# Group_9_Bastiaens_Castiaux_Danthine_Peti.net
KiCad netlist of a schematic drawn in EAGLE
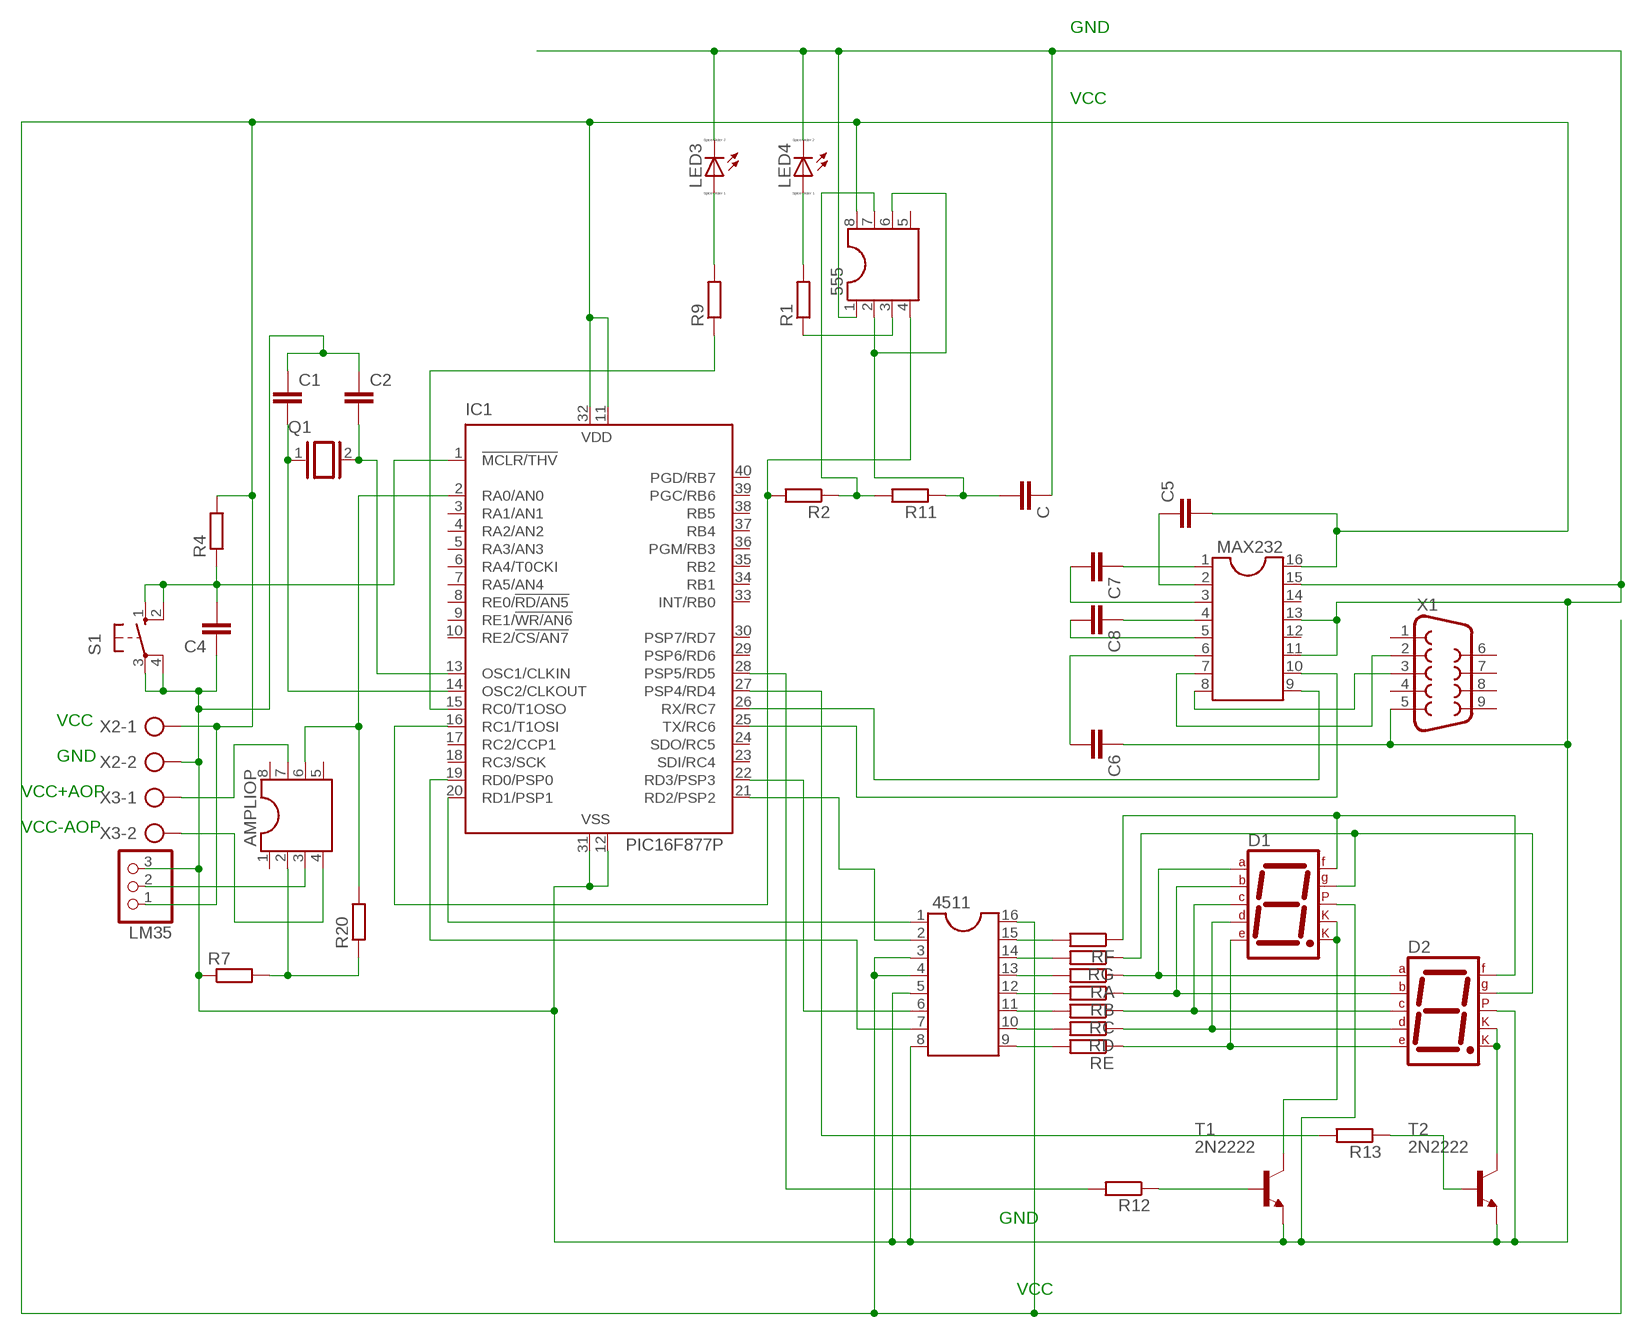
[diagram p0: schematic, sheet 1]

(export (version "E")
  (design (tool "Eeschema 10.0.6"))
  (components
    (comp (ref "555")
      (value "DIL8")
      (footprint "eagle-import:DIL08")
      (libsource (lib "eagle-import") (part "DIL8"))
    )
    (comp (ref "4511")
      (value "DIL16")
      (footprint "eagle-import:DIL16")
      (libsource (lib "eagle-import") (part "DIL16"))
    )
    (comp (ref "AMPLIOP")
      (value "DIL8")
      (footprint "eagle-import:DIL08")
      (libsource (lib "eagle-import") (part "DIL8"))
    )
    (comp (ref "C")
      (value "C-EU025-050X050")
      (footprint "eagle-import:C025-050X050")
      (libsource (lib "eagle-import") (part "C-EU025-050X050"))
    )
    (comp (ref "C1")
      (value "C-EU025-050X050")
      (footprint "eagle-import:C025-050X050")
      (libsource (lib "eagle-import") (part "C-EU025-050X050"))
    )
    (comp (ref "C2")
      (value "C-EU025-050X050")
      (footprint "eagle-import:C025-050X050")
      (libsource (lib "eagle-import") (part "C-EU025-050X050"))
    )
    (comp (ref "C4")
      (value "C-EU025-050X050")
      (footprint "eagle-import:C025-050X050")
      (libsource (lib "eagle-import") (part "C-EU025-050X050"))
    )
    (comp (ref "C5")
      (value "C-EU025-050X050")
      (footprint "eagle-import:C025-050X050")
      (libsource (lib "eagle-import") (part "C-EU025-050X050"))
    )
    (comp (ref "C6")
      (value "C-EU025-050X050")
      (footprint "eagle-import:C025-050X050")
      (libsource (lib "eagle-import") (part "C-EU025-050X050"))
    )
    (comp (ref "C7")
      (value "C-EU025-050X050")
      (footprint "eagle-import:C025-050X050")
      (libsource (lib "eagle-import") (part "C-EU025-050X050"))
    )
    (comp (ref "C8")
      (value "C-EU025-050X050")
      (footprint "eagle-import:C025-050X050")
      (libsource (lib "eagle-import") (part "C-EU025-050X050"))
    )
    (comp (ref "D1")
      (value "7SEG-CK")
      (footprint "eagle-import:7SEG-13")
      (libsource (lib "eagle-import") (part "7SEG-CK"))
    )
    (comp (ref "D2")
      (value "7SEG-CK")
      (footprint "eagle-import:7SEG-13")
      (libsource (lib "eagle-import") (part "7SEG-CK"))
    )
    (comp (ref "IC1")
      (value "PIC16F877P")
      (footprint "eagle-import:DIL40")
      (fields (field (name "MF") "MICROCHIP") (field (name "MPN") "PIC16F877-04/P"))
      (libsource (lib "eagle-import") (part "PIC16F87P7"))
    )
    (comp (ref "LED3")
      (value "LED_ELD260")
      (footprint "eagle-import:LED_LD260")
      (libsource (lib "eagle-import") (part "LED_ELD260"))
    )
    (comp (ref "LED4")
      (value "LED_ELD260")
      (footprint "eagle-import:LED_LD260")
      (libsource (lib "eagle-import") (part "LED_ELD260"))
    )
    (comp (ref "LM35")
      (value "PINHD-1X3")
      (footprint "eagle-import:1X03")
      (libsource (lib "eagle-import") (part "PINHD-1X3"))
    )
    (comp (ref "MAX232")
      (value "DIL16")
      (footprint "eagle-import:DIL16")
      (libsource (lib "eagle-import") (part "DIL16"))
    )
    (comp (ref "Q1")
      (value "XTAL/S")
      (footprint "eagle-import:QS")
      (libsource (lib "eagle-import") (part "XTAL/S"))
    )
    (comp (ref "R1")
      (value "R-EU_0204/7")
      (footprint "eagle-import:0204_7")
      (libsource (lib "eagle-import") (part "R-EU_0204/7"))
    )
    (comp (ref "R2")
      (value "R-EU_0204/7")
      (footprint "eagle-import:0204_7")
      (libsource (lib "eagle-import") (part "R-EU_0204/7"))
    )
    (comp (ref "R4")
      (value "R-EU_0204/7")
      (footprint "eagle-import:0204_7")
      (libsource (lib "eagle-import") (part "R-EU_0204/7"))
    )
    (comp (ref "R7")
      (value "R-EU_0204/7")
      (footprint "eagle-import:0204_7")
      (libsource (lib "eagle-import") (part "R-EU_0204/7"))
    )
    (comp (ref "R9")
      (value "R-EU_0204/7")
      (footprint "eagle-import:0204_7")
      (libsource (lib "eagle-import") (part "R-EU_0204/7"))
    )
    (comp (ref "R11")
      (value "R-EU_0204/7")
      (footprint "eagle-import:0204_7")
      (libsource (lib "eagle-import") (part "R-EU_0204/7"))
    )
    (comp (ref "R12")
      (value "R-EU_0204/7")
      (footprint "eagle-import:0204_7")
      (libsource (lib "eagle-import") (part "R-EU_0204/7"))
    )
    (comp (ref "R13")
      (value "R-EU_0204/7")
      (footprint "eagle-import:0204_7")
      (libsource (lib "eagle-import") (part "R-EU_0204/7"))
    )
    (comp (ref "R20")
      (value "R-EU_0204/7")
      (footprint "eagle-import:0204_7")
      (libsource (lib "eagle-import") (part "R-EU_0204/7"))
    )
    (comp (ref "RA")
      (value "R-EU_0204/7")
      (footprint "eagle-import:0204_7")
      (libsource (lib "eagle-import") (part "R-EU_0204/7"))
    )
    (comp (ref "RB")
      (value "R-EU_0204/7")
      (footprint "eagle-import:0204_7")
      (libsource (lib "eagle-import") (part "R-EU_0204/7"))
    )
    (comp (ref "RC")
      (value "R-EU_0204/7")
      (footprint "eagle-import:0204_7")
      (libsource (lib "eagle-import") (part "R-EU_0204/7"))
    )
    (comp (ref "RD")
      (value "R-EU_0204/7")
      (footprint "eagle-import:0204_7")
      (libsource (lib "eagle-import") (part "R-EU_0204/7"))
    )
    (comp (ref "RE")
      (value "R-EU_0204/7")
      (footprint "eagle-import:0204_7")
      (libsource (lib "eagle-import") (part "R-EU_0204/7"))
    )
    (comp (ref "RF")
      (value "R-EU_0204/7")
      (footprint "eagle-import:0204_7")
      (libsource (lib "eagle-import") (part "R-EU_0204/7"))
    )
    (comp (ref "RG")
      (value "R-EU_0204/7")
      (footprint "eagle-import:0204_7")
      (libsource (lib "eagle-import") (part "R-EU_0204/7"))
    )
    (comp (ref "S1")
      (value "10-XX")
      (footprint "eagle-import:B3F-10XX")
      (fields (field (name "MPN") "B3F-1000"))
      (libsource (lib "eagle-import") (part "10-XX"))
    )
    (comp (ref "T1")
      (value "2N2222")
      (footprint "eagle-import:TO18")
      (libsource (lib "eagle-import") (part "2N2222"))
    )
    (comp (ref "T2")
      (value "2N2222")
      (footprint "eagle-import:TO18")
      (libsource (lib "eagle-import") (part "2N2222"))
    )
    (comp (ref "X1")
      (value "F09V")
      (footprint "eagle-import:F09V")
      (libsource (lib "eagle-import") (part "F09V"))
    )
    (comp (ref "X2")
      (value "AK300/2")
      (footprint "eagle-import:AK300_2")
      (libsource (lib "eagle-import") (part "AK300/2"))
    )
    (comp (ref "X3")
      (value "AK300/2")
      (footprint "eagle-import:AK300_2")
      (libsource (lib "eagle-import") (part "AK300/2"))
    )
  )
  (nets
    (net (code "1") (name "Net-(555-Pad2)") (class "Default")
      (node (ref "555") (pin "2") (pinfunction "2_2") (pintype "passive"))
      (node (ref "555") (pin "6") (pinfunction "6_6") (pintype "passive"))
      (node (ref "C") (pin "2") (pinfunction "2_2") (pintype "passive"))
      (node (ref "R11") (pin "1") (pinfunction "1_1") (pintype "passive"))
    )
    (net (code "2") (name "Net-(555-Pad3)") (class "Default")
      (node (ref "555") (pin "3") (pinfunction "3_3") (pintype "passive"))
      (node (ref "R1") (pin "1") (pinfunction "1_1") (pintype "passive"))
    )
    (net (code "3") (name "Net-(555-Pad7)") (class "Default")
      (node (ref "555") (pin "7") (pinfunction "7_7") (pintype "passive"))
      (node (ref "R11") (pin "2") (pinfunction "2_2") (pintype "passive"))
      (node (ref "R2") (pin "1") (pinfunction "1_1") (pintype "passive"))
    )
    (net (code "4") (name "Net-(4511-Pad9)") (class "Default")
      (node (ref "4511") (pin "9") (pinfunction "9_9") (pintype "passive"))
      (node (ref "RE") (pin "2") (pinfunction "2_2") (pintype "passive"))
    )
    (net (code "5") (name "Net-(4511-Pad10)") (class "Default")
      (node (ref "4511") (pin "10") (pinfunction "10_10") (pintype "passive"))
      (node (ref "RD") (pin "2") (pinfunction "2_2") (pintype "passive"))
    )
    (net (code "6") (name "Net-(4511-Pad11)") (class "Default")
      (node (ref "4511") (pin "11") (pinfunction "11_11") (pintype "passive"))
      (node (ref "RC") (pin "2") (pinfunction "2_2") (pintype "passive"))
    )
    (net (code "7") (name "Net-(4511-Pad12)") (class "Default")
      (node (ref "4511") (pin "12") (pinfunction "12_12") (pintype "passive"))
      (node (ref "RB") (pin "2") (pinfunction "2_2") (pintype "passive"))
    )
    (net (code "8") (name "Net-(4511-Pad13)") (class "Default")
      (node (ref "4511") (pin "13") (pinfunction "13_13") (pintype "passive"))
      (node (ref "RA") (pin "2") (pinfunction "2_2") (pintype "passive"))
    )
    (net (code "9") (name "Net-(4511-Pad14)") (class "Default")
      (node (ref "4511") (pin "14") (pinfunction "14_14") (pintype "passive"))
      (node (ref "RG") (pin "2") (pinfunction "2_2") (pintype "passive"))
    )
    (net (code "10") (name "Net-(4511-Pad15)") (class "Default")
      (node (ref "4511") (pin "15") (pinfunction "15_15") (pintype "passive"))
      (node (ref "RF") (pin "2") (pinfunction "2_2") (pintype "passive"))
    )
    (net (code "11") (name "Net-(AMPLIOP-Pad2)") (class "Default")
      (node (ref "AMPLIOP") (pin "2") (pinfunction "2_2") (pintype "passive"))
      (node (ref "R20") (pin "1") (pinfunction "1_1") (pintype "passive"))
      (node (ref "R7") (pin "2") (pinfunction "2_2") (pintype "passive"))
    )
    (net (code "12") (name "Net-(AMPLIOP-Pad3)") (class "Default")
      (node (ref "AMPLIOP") (pin "3") (pinfunction "3_3") (pintype "passive"))
      (node (ref "LM35") (pin "2") (pinfunction "2_2") (pintype "passive"))
    )
    (net (code "13") (name "Net-(C5-Pad1)") (class "Default")
      (node (ref "C5") (pin "1") (pinfunction "1_1") (pintype "passive"))
      (node (ref "MAX232") (pin "2") (pinfunction "2_2") (pintype "passive"))
    )
    (net (code "14") (name "Net-(C6-Pad2)") (class "Default")
      (node (ref "C6") (pin "2") (pinfunction "2_2") (pintype "passive"))
      (node (ref "MAX232") (pin "6") (pinfunction "6_6") (pintype "passive"))
    )
    (net (code "15") (name "Net-(C7-Pad1)") (class "Default")
      (node (ref "C7") (pin "1") (pinfunction "1_1") (pintype "passive"))
      (node (ref "MAX232") (pin "1") (pinfunction "1_1") (pintype "passive"))
    )
    (net (code "16") (name "Net-(C7-Pad2)") (class "Default")
      (node (ref "C7") (pin "2") (pinfunction "2_2") (pintype "passive"))
      (node (ref "MAX232") (pin "3") (pinfunction "3_3") (pintype "passive"))
    )
    (net (code "17") (name "Net-(C8-Pad1)") (class "Default")
      (node (ref "C8") (pin "1") (pinfunction "1_1") (pintype "passive"))
      (node (ref "MAX232") (pin "4") (pinfunction "4_4") (pintype "passive"))
    )
    (net (code "18") (name "Net-(C8-Pad2)") (class "Default")
      (node (ref "C8") (pin "2") (pinfunction "2_2") (pintype "passive"))
      (node (ref "MAX232") (pin "5") (pinfunction "5_5") (pintype "passive"))
    )
    (net (code "19") (name "Net-(D1-A)") (class "Default")
      (node (ref "D1") (pin "7") (pinfunction "A_7") (pintype "passive"))
      (node (ref "D2") (pin "7") (pinfunction "A_7") (pintype "passive"))
      (node (ref "RA") (pin "1") (pinfunction "1_1") (pintype "passive"))
    )
    (net (code "20") (name "Net-(D1-B)") (class "Default")
      (node (ref "D1") (pin "6") (pinfunction "B_6") (pintype "passive"))
      (node (ref "D2") (pin "6") (pinfunction "B_6") (pintype "passive"))
      (node (ref "RB") (pin "1") (pinfunction "1_1") (pintype "passive"))
    )
    (net (code "21") (name "Net-(D1-C)") (class "Default")
      (node (ref "D1") (pin "4") (pinfunction "C_4") (pintype "passive"))
      (node (ref "D2") (pin "4") (pinfunction "C_4") (pintype "passive"))
      (node (ref "RC") (pin "1") (pinfunction "1_1") (pintype "passive"))
    )
    (net (code "22") (name "Net-(D1-CK1)") (class "Default")
      (node (ref "D1") (pin "3") (pinfunction "CK1_3") (pintype "passive"))
      (node (ref "D1") (pin "8") (pinfunction "CK2_8") (pintype "passive"))
      (node (ref "T1") (pin "3") (pinfunction "C_3") (pintype "passive"))
    )
    (net (code "23") (name "Net-(D1-D)") (class "Default")
      (node (ref "D1") (pin "2") (pinfunction "D_2") (pintype "passive"))
      (node (ref "D2") (pin "2") (pinfunction "D_2") (pintype "passive"))
      (node (ref "RD") (pin "1") (pinfunction "1_1") (pintype "passive"))
    )
    (net (code "24") (name "Net-(D1-DP)") (class "Default")
      (node (ref "4511") (pin "5") (pinfunction "5_5") (pintype "passive"))
      (node (ref "4511") (pin "8") (pinfunction "8_8") (pintype "passive"))
      (node (ref "555") (pin "1") (pinfunction "1_1") (pintype "passive"))
      (node (ref "C") (pin "1") (pinfunction "1_1") (pintype "passive"))
      (node (ref "C1") (pin "1") (pinfunction "1_1") (pintype "passive"))
      (node (ref "C2") (pin "1") (pinfunction "1_1") (pintype "passive"))
      (node (ref "C4") (pin "1") (pinfunction "1_1") (pintype "passive"))
      (node (ref "C6") (pin "1") (pinfunction "1_1") (pintype "passive"))
      (node (ref "D1") (pin "5") (pinfunction "DP_5") (pintype "passive"))
      (node (ref "D2") (pin "5") (pinfunction "DP_5") (pintype "passive"))
      (node (ref "IC1") (pin "12") (pinfunction "VSS_12") (pintype "power_in"))
      (node (ref "IC1") (pin "31") (pinfunction "VSS_31") (pintype "power_in"))
      (node (ref "LED3") (pin "K") (pinfunction "C_K") (pintype "passive"))
      (node (ref "LED4") (pin "K") (pinfunction "C_K") (pintype "passive"))
      (node (ref "LM35") (pin "3") (pinfunction "3_3") (pintype "passive"))
      (node (ref "MAX232") (pin "11") (pinfunction "11_11") (pintype "passive"))
      (node (ref "MAX232") (pin "13") (pinfunction "13_13") (pintype "passive"))
      (node (ref "MAX232") (pin "15") (pinfunction "15_15") (pintype "passive"))
      (node (ref "R7") (pin "1") (pinfunction "1_1") (pintype "passive"))
      (node (ref "S1") (pin "3") (pinfunction "P_3") (pintype "passive"))
      (node (ref "S1") (pin "4") (pinfunction "P1_4") (pintype "passive"))
      (node (ref "T1") (pin "1") (pinfunction "E_1") (pintype "passive"))
      (node (ref "T2") (pin "1") (pinfunction "E_1") (pintype "passive"))
      (node (ref "X1") (pin "5") (pinfunction "5_5") (pintype "passive"))
      (node (ref "X2") (pin "2") (pinfunction "KL_2") (pintype "passive"))
    )
    (net (code "25") (name "Net-(D1-E)") (class "Default")
      (node (ref "D1") (pin "1") (pinfunction "E_1") (pintype "passive"))
      (node (ref "D2") (pin "1") (pinfunction "E_1") (pintype "passive"))
      (node (ref "RE") (pin "1") (pinfunction "1_1") (pintype "passive"))
    )
    (net (code "26") (name "Net-(D1-F)") (class "Default")
      (node (ref "D1") (pin "9") (pinfunction "F_9") (pintype "passive"))
      (node (ref "D2") (pin "9") (pinfunction "F_9") (pintype "passive"))
      (node (ref "RF") (pin "1") (pinfunction "1_1") (pintype "passive"))
    )
    (net (code "27") (name "Net-(D1-G)") (class "Default")
      (node (ref "D1") (pin "10") (pinfunction "G_10") (pintype "passive"))
      (node (ref "D2") (pin "10") (pinfunction "G_10") (pintype "passive"))
      (node (ref "RG") (pin "1") (pinfunction "1_1") (pintype "passive"))
    )
    (net (code "28") (name "Net-(D2-CK1)") (class "Default")
      (node (ref "D2") (pin "3") (pinfunction "CK1_3") (pintype "passive"))
      (node (ref "D2") (pin "8") (pinfunction "CK2_8") (pintype "passive"))
      (node (ref "T2") (pin "3") (pinfunction "C_3") (pintype "passive"))
    )
    (net (code "29") (name "Net-(IC1-OSC1{slash}CLKIN)") (class "Default")
      (node (ref "C2") (pin "2") (pinfunction "2_2") (pintype "passive"))
      (node (ref "IC1") (pin "13") (pinfunction "OSC1/CLKIN_13") (pintype "input"))
      (node (ref "Q1") (pin "2") (pinfunction "2_2") (pintype "passive"))
    )
    (net (code "30") (name "Net-(IC1-OSC2{slash}CLKOUT)") (class "Default")
      (node (ref "C1") (pin "2") (pinfunction "2_2") (pintype "passive"))
      (node (ref "IC1") (pin "14") (pinfunction "OSC2/CLKOUT_14") (pintype "output"))
      (node (ref "Q1") (pin "1") (pinfunction "1_1") (pintype "passive"))
    )
    (net (code "31") (name "Net-(IC1-PSP4{slash}RD4)") (class "Default")
      (node (ref "IC1") (pin "27") (pinfunction "PSP4/RD4_27") (pintype "bidirectional"))
      (node (ref "R13") (pin "2") (pinfunction "2_2") (pintype "passive"))
    )
    (net (code "32") (name "Net-(IC1-PSP5{slash}RD5)") (class "Default")
      (node (ref "IC1") (pin "28") (pinfunction "PSP5/RD5_28") (pintype "bidirectional"))
      (node (ref "R12") (pin "2") (pinfunction "2_2") (pintype "passive"))
    )
    (net (code "33") (name "Net-(IC1-RA0{slash}AN0)") (class "Default")
      (node (ref "AMPLIOP") (pin "6") (pinfunction "6_6") (pintype "passive"))
      (node (ref "IC1") (pin "2") (pinfunction "RA0/AN0_2") (pintype "bidirectional"))
      (node (ref "R20") (pin "2") (pinfunction "2_2") (pintype "passive"))
    )
    (net (code "34") (name "Net-(IC1-RC0{slash}T1OSO)") (class "Default")
      (node (ref "IC1") (pin "15") (pinfunction "RC0/T1OSO_15") (pintype "bidirectional"))
      (node (ref "R9") (pin "1") (pinfunction "1_1") (pintype "passive"))
    )
    (net (code "35") (name "Net-(IC1-RC1{slash}T1OSI)") (class "Default")
      (node (ref "555") (pin "4") (pinfunction "4_4") (pintype "passive"))
      (node (ref "IC1") (pin "16") (pinfunction "RC1/T1OSI_16") (pintype "bidirectional"))
      (node (ref "R2") (pin "2") (pinfunction "2_2") (pintype "passive"))
    )
    (net (code "36") (name "Net-(IC1-RD0{slash}PSP0)") (class "Default")
      (node (ref "4511") (pin "7") (pinfunction "7_7") (pintype "passive"))
      (node (ref "IC1") (pin "19") (pinfunction "RD0/PSP0_19") (pintype "bidirectional"))
    )
    (net (code "37") (name "Net-(IC1-RD1{slash}PSP1)") (class "Default")
      (node (ref "4511") (pin "1") (pinfunction "1_1") (pintype "passive"))
      (node (ref "IC1") (pin "20") (pinfunction "RD1/PSP1_20") (pintype "bidirectional"))
    )
    (net (code "38") (name "Net-(IC1-RD2{slash}PSP2)") (class "Default")
      (node (ref "4511") (pin "2") (pinfunction "2_2") (pintype "passive"))
      (node (ref "IC1") (pin "21") (pinfunction "RD2/PSP2_21") (pintype "bidirectional"))
    )
    (net (code "39") (name "Net-(IC1-RD3{slash}PSP3)") (class "Default")
      (node (ref "4511") (pin "6") (pinfunction "6_6") (pintype "passive"))
      (node (ref "IC1") (pin "22") (pinfunction "RD3/PSP3_22") (pintype "bidirectional"))
    )
    (net (code "40") (name "Net-(IC1-RX{slash}RC7)") (class "Default")
      (node (ref "IC1") (pin "26") (pinfunction "RX/RC7_26") (pintype "bidirectional"))
      (node (ref "MAX232") (pin "9") (pinfunction "9_9") (pintype "passive"))
    )
    (net (code "41") (name "Net-(IC1-TX{slash}RC6)") (class "Default")
      (node (ref "IC1") (pin "25") (pinfunction "TX/RC6_25") (pintype "bidirectional"))
      (node (ref "MAX232") (pin "10") (pinfunction "10_10") (pintype "passive"))
    )
    (net (code "42") (name "Net-(IC1-~{MCLR{slash}THV})") (class "Default")
      (node (ref "C4") (pin "2") (pinfunction "2_2") (pintype "passive"))
      (node (ref "IC1") (pin "1") (pinfunction "~{MCLR/THV}_1") (pintype "input"))
      (node (ref "R4") (pin "1") (pinfunction "1_1") (pintype "passive"))
      (node (ref "S1") (pin "1") (pinfunction "S_1") (pintype "passive"))
      (node (ref "S1") (pin "2") (pinfunction "S1_2") (pintype "passive"))
    )
    (net (code "43") (name "Net-(LED3-PadA)") (class "Default")
      (node (ref "LED3") (pin "A") (pinfunction "A_A") (pintype "passive"))
      (node (ref "R9") (pin "2") (pinfunction "2_2") (pintype "passive"))
    )
    (net (code "44") (name "Net-(LED4-PadA)") (class "Default")
      (node (ref "LED4") (pin "A") (pinfunction "A_A") (pintype "passive"))
      (node (ref "R1") (pin "2") (pinfunction "2_2") (pintype "passive"))
    )
    (net (code "45") (name "Net-(MAX232-Pad7)") (class "Default")
      (node (ref "MAX232") (pin "7") (pinfunction "7_7") (pintype "passive"))
      (node (ref "X1") (pin "2") (pinfunction "2_2") (pintype "passive"))
    )
    (net (code "46") (name "Net-(MAX232-Pad8)") (class "Default")
      (node (ref "MAX232") (pin "8") (pinfunction "8_8") (pintype "passive"))
      (node (ref "X1") (pin "3") (pinfunction "3_3") (pintype "passive"))
    )
    (net (code "47") (name "Net-(T1-B)") (class "Default")
      (node (ref "R12") (pin "1") (pinfunction "1_1") (pintype "passive"))
      (node (ref "T1") (pin "2") (pinfunction "B_2") (pintype "passive"))
    )
    (net (code "48") (name "Net-(T2-B)") (class "Default")
      (node (ref "R13") (pin "1") (pinfunction "1_1") (pintype "passive"))
      (node (ref "T2") (pin "2") (pinfunction "B_2") (pintype "passive"))
    )
    (net (code "49") (name "Net-(X2A-KL)") (class "Default")
      (node (ref "4511") (pin "16") (pinfunction "16_16") (pintype "passive"))
      (node (ref "4511") (pin "3") (pinfunction "3_3") (pintype "passive"))
      (node (ref "4511") (pin "4") (pinfunction "4_4") (pintype "passive"))
      (node (ref "555") (pin "8") (pinfunction "8_8") (pintype "passive"))
      (node (ref "C5") (pin "2") (pinfunction "2_2") (pintype "passive"))
      (node (ref "IC1") (pin "11") (pinfunction "VDD_11") (pintype "power_in"))
      (node (ref "IC1") (pin "32") (pinfunction "VDD_32") (pintype "power_in"))
      (node (ref "LM35") (pin "1") (pinfunction "1_1") (pintype "passive"))
      (node (ref "MAX232") (pin "16") (pinfunction "16_16") (pintype "passive"))
      (node (ref "R4") (pin "2") (pinfunction "2_2") (pintype "passive"))
      (node (ref "X2") (pin "1") (pinfunction "KL_1") (pintype "passive"))
    )
    (net (code "50") (name "Net-(X3A-KL)") (class "Default")
      (node (ref "AMPLIOP") (pin "7") (pinfunction "7_7") (pintype "passive"))
      (node (ref "X3") (pin "1") (pinfunction "KL_1") (pintype "passive"))
    )
    (net (code "51") (name "Net-(X3B-KL)") (class "Default")
      (node (ref "AMPLIOP") (pin "4") (pinfunction "4_4") (pintype "passive"))
      (node (ref "X3") (pin "2") (pinfunction "KL_2") (pintype "passive"))
    )
    (net (code "52") (name "unconnected-(555-Pad5)") (class "Default")
      (node (ref "555") (pin "5") (pinfunction "5_5") (pintype "passive"))
    )
    (net (code "53") (name "unconnected-(AMPLIOP-Pad1)") (class "Default")
      (node (ref "AMPLIOP") (pin "1") (pinfunction "1_1") (pintype "passive"))
    )
    (net (code "54") (name "unconnected-(AMPLIOP-Pad5)") (class "Default")
      (node (ref "AMPLIOP") (pin "5") (pinfunction "5_5") (pintype "passive"))
    )
    (net (code "55") (name "unconnected-(AMPLIOP-Pad8)") (class "Default")
      (node (ref "AMPLIOP") (pin "8") (pinfunction "8_8") (pintype "passive"))
    )
    (net (code "56") (name "unconnected-(IC1-INT{slash}RB0-Pad33)") (class "Default")
      (node (ref "IC1") (pin "33") (pinfunction "INT/RB0_33") (pintype "bidirectional"))
    )
    (net (code "57") (name "unconnected-(IC1-PGC{slash}RB6-Pad39)") (class "Default")
      (node (ref "IC1") (pin "39") (pinfunction "PGC/RB6_39") (pintype "bidirectional"))
    )
    (net (code "58") (name "unconnected-(IC1-PGD{slash}RB7-Pad40)") (class "Default")
      (node (ref "IC1") (pin "40") (pinfunction "PGD/RB7_40") (pintype "bidirectional"))
    )
    (net (code "59") (name "unconnected-(IC1-PGM{slash}RB3-Pad36)") (class "Default")
      (node (ref "IC1") (pin "36") (pinfunction "PGM/RB3_36") (pintype "bidirectional"))
    )
    (net (code "60") (name "unconnected-(IC1-PSP6{slash}RD6-Pad29)") (class "Default")
      (node (ref "IC1") (pin "29") (pinfunction "PSP6/RD6_29") (pintype "bidirectional"))
    )
    (net (code "61") (name "unconnected-(IC1-PSP7{slash}RD7-Pad30)") (class "Default")
      (node (ref "IC1") (pin "30") (pinfunction "PSP7/RD7_30") (pintype "bidirectional"))
    )
    (net (code "62") (name "unconnected-(IC1-RA1{slash}AN1-Pad3)") (class "Default")
      (node (ref "IC1") (pin "3") (pinfunction "RA1/AN1_3") (pintype "bidirectional"))
    )
    (net (code "63") (name "unconnected-(IC1-RA2{slash}AN2-Pad4)") (class "Default")
      (node (ref "IC1") (pin "4") (pinfunction "RA2/AN2_4") (pintype "bidirectional"))
    )
    (net (code "64") (name "unconnected-(IC1-RA3{slash}AN3-Pad5)") (class "Default")
      (node (ref "IC1") (pin "5") (pinfunction "RA3/AN3_5") (pintype "bidirectional"))
    )
    (net (code "65") (name "unconnected-(IC1-RA4{slash}T0CKI-Pad6)") (class "Default")
      (node (ref "IC1") (pin "6") (pinfunction "RA4/T0CKI_6") (pintype "bidirectional"))
    )
    (net (code "66") (name "unconnected-(IC1-RA5{slash}AN4-Pad7)") (class "Default")
      (node (ref "IC1") (pin "7") (pinfunction "RA5/AN4_7") (pintype "bidirectional"))
    )
    (net (code "67") (name "unconnected-(IC1-RB1-Pad34)") (class "Default")
      (node (ref "IC1") (pin "34") (pinfunction "RB1_34") (pintype "bidirectional"))
    )
    (net (code "68") (name "unconnected-(IC1-RB2-Pad35)") (class "Default")
      (node (ref "IC1") (pin "35") (pinfunction "RB2_35") (pintype "bidirectional"))
    )
    (net (code "69") (name "unconnected-(IC1-RB4-Pad37)") (class "Default")
      (node (ref "IC1") (pin "37") (pinfunction "RB4_37") (pintype "bidirectional"))
    )
    (net (code "70") (name "unconnected-(IC1-RB5-Pad38)") (class "Default")
      (node (ref "IC1") (pin "38") (pinfunction "RB5_38") (pintype "bidirectional"))
    )
    (net (code "71") (name "unconnected-(IC1-RC2{slash}CCP1-Pad17)") (class "Default")
      (node (ref "IC1") (pin "17") (pinfunction "RC2/CCP1_17") (pintype "bidirectional"))
    )
    (net (code "72") (name "unconnected-(IC1-RC3{slash}SCK-Pad18)") (class "Default")
      (node (ref "IC1") (pin "18") (pinfunction "RC3/SCK_18") (pintype "bidirectional"))
    )
    (net (code "73") (name "unconnected-(IC1-RE0{slash}~{RD{slash}AN5}-Pad8)") (class "Default")
      (node (ref "IC1") (pin "8") (pinfunction "RE0/~{RD/AN5}_8") (pintype "bidirectional"))
    )
    (net (code "74") (name "unconnected-(IC1-RE1{slash}~{WR{slash}AN6}-Pad9)") (class "Default")
      (node (ref "IC1") (pin "9") (pinfunction "RE1/~{WR/AN6}_9") (pintype "bidirectional"))
    )
    (net (code "75") (name "unconnected-(IC1-RE2{slash}~{CS{slash}AN7}-Pad10)") (class "Default")
      (node (ref "IC1") (pin "10") (pinfunction "RE2/~{CS/AN7}_10") (pintype "bidirectional"))
    )
    (net (code "76") (name "unconnected-(IC1-SDI{slash}RC4-Pad23)") (class "Default")
      (node (ref "IC1") (pin "23") (pinfunction "SDI/RC4_23") (pintype "bidirectional"))
    )
    (net (code "77") (name "unconnected-(IC1-SDO{slash}RC5-Pad24)") (class "Default")
      (node (ref "IC1") (pin "24") (pinfunction "SDO/RC5_24") (pintype "bidirectional"))
    )
    (net (code "78") (name "unconnected-(MAX232-Pad12)") (class "Default")
      (node (ref "MAX232") (pin "12") (pinfunction "12_12") (pintype "passive"))
    )
    (net (code "79") (name "unconnected-(MAX232-Pad14)") (class "Default")
      (node (ref "MAX232") (pin "14") (pinfunction "14_14") (pintype "passive"))
    )
    (net (code "80") (name "unconnected-(X1-Pad1)") (class "Default")
      (node (ref "X1") (pin "1") (pinfunction "1_1") (pintype "passive"))
    )
    (net (code "81") (name "unconnected-(X1-Pad4)") (class "Default")
      (node (ref "X1") (pin "4") (pinfunction "4_4") (pintype "passive"))
    )
    (net (code "82") (name "unconnected-(X1-Pad6)") (class "Default")
      (node (ref "X1") (pin "6") (pinfunction "6_6") (pintype "passive"))
    )
    (net (code "83") (name "unconnected-(X1-Pad7)") (class "Default")
      (node (ref "X1") (pin "7") (pinfunction "7_7") (pintype "passive"))
    )
    (net (code "84") (name "unconnected-(X1-Pad8)") (class "Default")
      (node (ref "X1") (pin "8") (pinfunction "8_8") (pintype "passive"))
    )
    (net (code "85") (name "unconnected-(X1-Pad9)") (class "Default")
      (node (ref "X1") (pin "9") (pinfunction "9_9") (pintype "passive"))
    )
  )
)
